# Terminal.net
KiCad netlist of a schematic drawn in Altium Designer
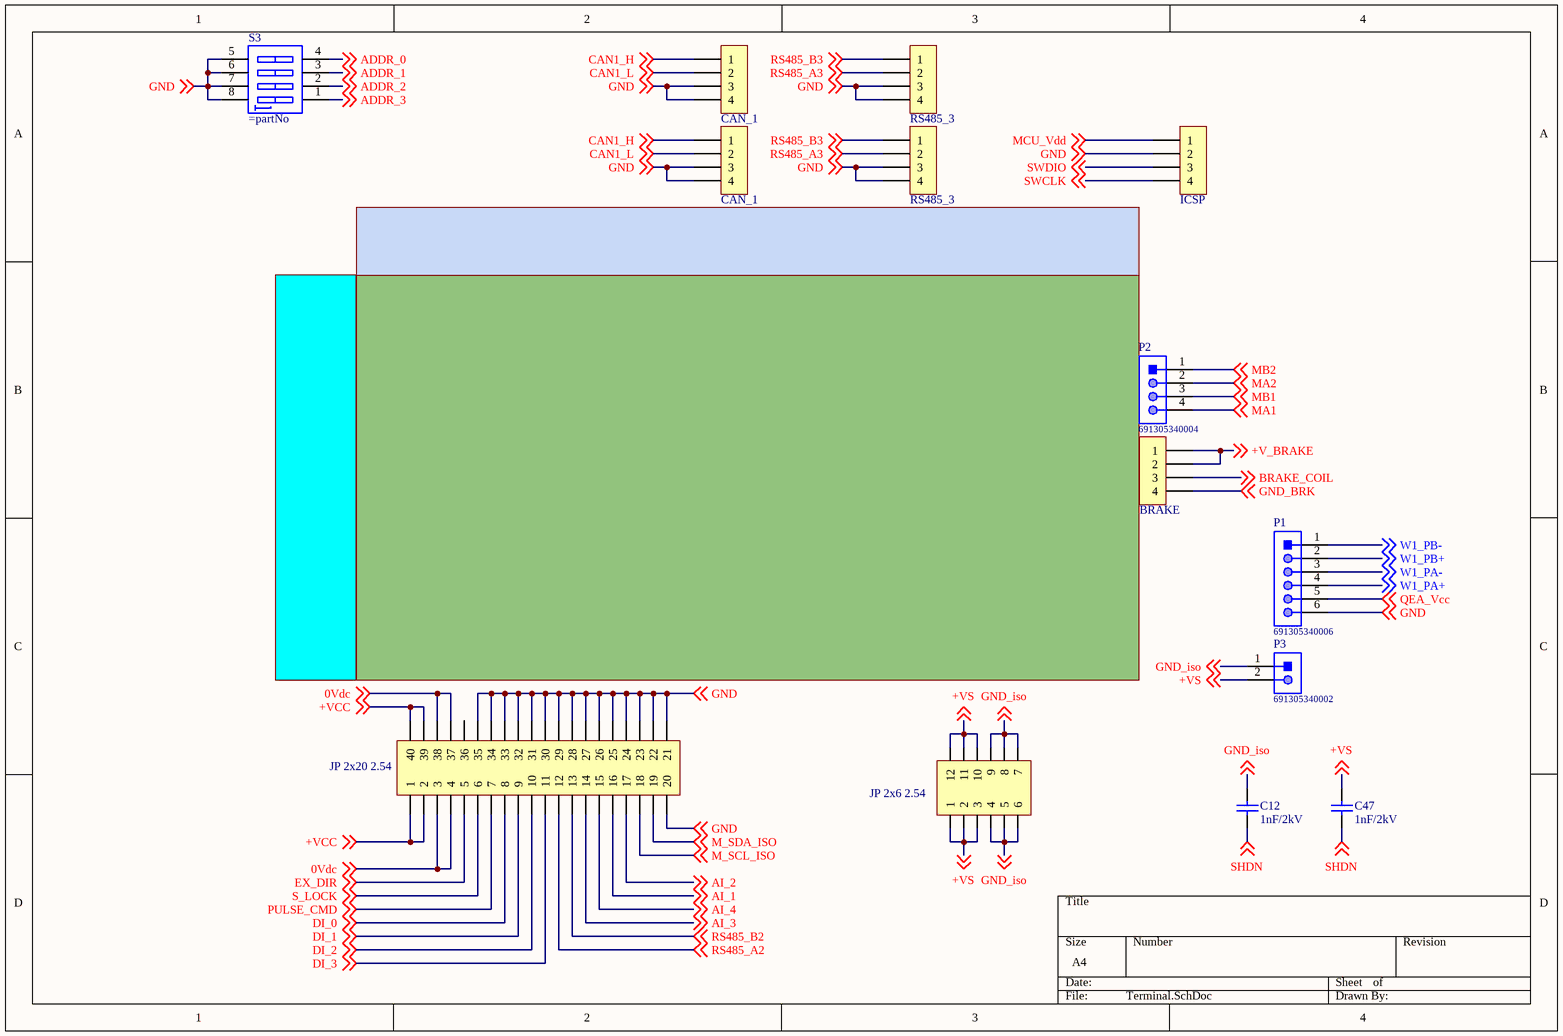
[diagram p0: Terminal.SchDoc]

(export (version "E")
  (design (tool "Eeschema 10.0.6"))
  (components
    (comp (ref "C12")
      (value "1nF/2kV")
      (footprint "Cap 3KV 5mm")
      (description "Capacitor")
      (fields (field (name "PUBLISHER") "Altium Limited"))
      (libsource (lib "DoHuong_sch") (part "Cap"))
    )
    (comp (ref "C47")
      (value "1nF/2kV")
      (footprint "Cap 3KV 5mm")
      (description "Capacitor")
      (fields (field (name "PUBLISHER") "Altium Limited"))
      (libsource (lib "DoHuong_sch") (part "Cap"))
    )
    (comp (ref "H1")
      (value "CAN_1")
      (footprint "Header 4P DC 2.54")
      (description "Cắm")
      (libsource (lib "Header") (part "Header 4P 2.54 Duc Cong"))
    )
    (comp (ref "H2")
      (value "RS485_3")
      (footprint "Header 4P DC 2.54")
      (description "Cắm")
      (libsource (lib "Header") (part "Header 4P 2.54 Duc Cong"))
    )
    (comp (ref "H4")
      (value "ICSP")
      (footprint "Header 4P DC 2.54")
      (description "Cắm")
      (libsource (lib "Header") (part "Header 4P 2.54 Duc Cong"))
    )
    (comp (ref "H5")
      (value "BRAKE")
      (footprint "Header 4P DC 2.54")
      (description "Cắm")
      (libsource (lib "") (part "Header 4P 2.54 Duc Cong_1"))
    )
    (comp (ref "H6")
      (value "CAN_1")
      (footprint "Header 4P DC 2.54")
      (description "Cắm")
      (libsource (lib "Header") (part "Header 4P 2.54 Duc Cong"))
    )
    (comp (ref "H8")
      (value "RS485_3")
      (footprint "Header 4P DC 2.54")
      (description "Cắm")
      (libsource (lib "Header") (part "Header 4P 2.54 Duc Cong"))
    )
    (comp (ref "JP1")
      (value "JP 2x20 2.54")
      (footprint "JP 2x20 DC")
      (description "Cắm")
      (libsource (lib "Jump") (part "JP 2x20 2.54 Duc Cong"))
    )
    (comp (ref "JP2")
      (value "JP 2x6 2.54")
      (footprint "JP 2x6 DC")
      (description "Cắm")
      (libsource (lib "Jump") (part "JP 2x6 2.54 Duc Cong"))
    )
    (comp (ref "P1")
      (value "691305340006")
      (footprint "691305340006")
      (description "Serie 3053 - 3.81mm Horizontal PCB Header with Plastic Latch WR-TBL, 6 pin")
      (fields (field (name "PUBLISHER") "Wurth Elektronik"))
      (libsource (lib "Altium_TBL_Pluggable_PCB_System (rev18a)") (part "691305340006"))
    )
    (comp (ref "P2")
      (value "691305340004")
      (footprint "691305340004")
      (description "Serie 3053 - 3.81mm Horizontal PCB Header with Plastic Latch WR-TBL, 4 pin")
      (fields (field (name "PUBLISHER") "Wurth Elektronik"))
      (libsource (lib "Altium_TBL_Pluggable_PCB_System (rev18a)") (part "691305340004"))
    )
    (comp (ref "P3")
      (value "691305340002")
      (footprint "691305340002")
      (description "Serie 3053 - 3.81mm Horizontal PCB Header with Plastic Latch WR-TBL, 2 pin")
      (fields (field (name "PUBLISHER") "Wurth Elektronik"))
      (libsource (lib "Altium_TBL_Pluggable_PCB_System (rev18a)") (part "691305340002"))
    )
    (comp (ref "S3")
      (value "~")
      (footprint "SW-DIP4")
      (description "WS-DITV 2.54 mm small compact THT flat actuator with top tape")
      (fields
        (field (name "MANUFACTURER") "Wurth Elektronik")
        (field (name "PART NO.") "418127160904")
        (field (name "CREATED BY") "Baojun Chen")
      )
      (libsource (lib "LIBRARY") (part "SWDIP4"))
    )
  )
  (nets
    (net (code "1") (name "+VCC") (class "Default")
      (node (ref "JP1") (pin "1") (pinfunction "1_1") (pintype "passive"))
      (node (ref "JP1") (pin "2") (pinfunction "2_2") (pintype "passive"))
      (node (ref "JP1") (pin "39") (pinfunction "39_39") (pintype "passive"))
      (node (ref "JP1") (pin "40") (pinfunction "40_40") (pintype "passive"))
    )
    (net (code "2") (name "+VS") (class "Default")
      (node (ref "C47") (pin "2") (pinfunction "2_2") (pintype "passive"))
      (node (ref "JP2") (pin "1") (pinfunction "1_1") (pintype "passive"))
      (node (ref "JP2") (pin "10") (pinfunction "10_10") (pintype "passive"))
      (node (ref "JP2") (pin "11") (pinfunction "11_11") (pintype "passive"))
      (node (ref "JP2") (pin "12") (pinfunction "12_12") (pintype "passive"))
      (node (ref "JP2") (pin "2") (pinfunction "2_2") (pintype "passive"))
      (node (ref "JP2") (pin "3") (pinfunction "3_3") (pintype "passive"))
      (node (ref "P3") (pin "2") (pinfunction "2_2") (pintype "passive"))
    )
    (net (code "3") (name "+V_BRAKE") (class "Default")
      (node (ref "H5") (pin "1") (pinfunction "1_1") (pintype "passive"))
      (node (ref "H5") (pin "2") (pinfunction "2_2") (pintype "passive"))
    )
    (net (code "4") (name "0Vdc") (class "Default")
      (node (ref "JP1") (pin "3") (pinfunction "3_3") (pintype "passive"))
      (node (ref "JP1") (pin "37") (pinfunction "37_37") (pintype "passive"))
      (node (ref "JP1") (pin "38") (pinfunction "38_38") (pintype "passive"))
      (node (ref "JP1") (pin "4") (pinfunction "4_4") (pintype "passive"))
    )
    (net (code "5") (name "ADDR_0") (class "Default")
      (node (ref "S3") (pin "4") (pinfunction "4_4") (pintype "passive"))
    )
    (net (code "6") (name "ADDR_1") (class "Default")
      (node (ref "S3") (pin "3") (pinfunction "3_3") (pintype "passive"))
    )
    (net (code "7") (name "ADDR_2") (class "Default")
      (node (ref "S3") (pin "2") (pinfunction "2_2") (pintype "passive"))
    )
    (net (code "8") (name "ADDR_3") (class "Default")
      (node (ref "S3") (pin "1") (pinfunction "1_1") (pintype "passive"))
    )
    (net (code "9") (name "AI_1") (class "Default")
      (node (ref "JP1") (pin "16") (pinfunction "16_16") (pintype "passive"))
    )
    (net (code "10") (name "AI_2") (class "Default")
      (node (ref "JP1") (pin "17") (pinfunction "17_17") (pintype "passive"))
    )
    (net (code "11") (name "AI_3") (class "Default")
      (node (ref "JP1") (pin "14") (pinfunction "14_14") (pintype "passive"))
    )
    (net (code "12") (name "AI_4") (class "Default")
      (node (ref "JP1") (pin "15") (pinfunction "15_15") (pintype "passive"))
    )
    (net (code "13") (name "BRAKE_COIL") (class "Default")
      (node (ref "H5") (pin "3") (pinfunction "3_3") (pintype "passive"))
    )
    (net (code "14") (name "CAN1_H") (class "Default")
      (node (ref "H1") (pin "1") (pinfunction "1_1") (pintype "passive"))
      (node (ref "H6") (pin "1") (pinfunction "1_1") (pintype "passive"))
    )
    (net (code "15") (name "CAN1_L") (class "Default")
      (node (ref "H1") (pin "2") (pinfunction "2_2") (pintype "passive"))
      (node (ref "H6") (pin "2") (pinfunction "2_2") (pintype "passive"))
    )
    (net (code "16") (name "DI_0") (class "Default")
      (node (ref "JP1") (pin "8") (pinfunction "8_8") (pintype "passive"))
    )
    (net (code "17") (name "DI_1") (class "Default")
      (node (ref "JP1") (pin "9") (pinfunction "9_9") (pintype "passive"))
    )
    (net (code "18") (name "DI_2") (class "Default")
      (node (ref "JP1") (pin "10") (pinfunction "10_10") (pintype "passive"))
    )
    (net (code "19") (name "DI_3") (class "Default")
      (node (ref "JP1") (pin "11") (pinfunction "11_11") (pintype "passive"))
    )
    (net (code "20") (name "EX_DIR") (class "Default")
      (node (ref "JP1") (pin "5") (pinfunction "5_5") (pintype "passive"))
    )
    (net (code "21") (name "GND") (class "Default")
      (node (ref "H1") (pin "3") (pinfunction "3_3") (pintype "passive"))
      (node (ref "H1") (pin "4") (pinfunction "4_4") (pintype "passive"))
      (node (ref "H2") (pin "3") (pinfunction "3_3") (pintype "passive"))
      (node (ref "H2") (pin "4") (pinfunction "4_4") (pintype "passive"))
      (node (ref "H4") (pin "2") (pinfunction "2_2") (pintype "passive"))
      (node (ref "H6") (pin "3") (pinfunction "3_3") (pintype "passive"))
      (node (ref "H6") (pin "4") (pinfunction "4_4") (pintype "passive"))
      (node (ref "H8") (pin "3") (pinfunction "3_3") (pintype "passive"))
      (node (ref "H8") (pin "4") (pinfunction "4_4") (pintype "passive"))
      (node (ref "JP1") (pin "20") (pinfunction "20_20") (pintype "passive"))
      (node (ref "JP1") (pin "21") (pinfunction "21_21") (pintype "passive"))
      (node (ref "JP1") (pin "22") (pinfunction "22_22") (pintype "passive"))
      (node (ref "JP1") (pin "23") (pinfunction "23_23") (pintype "passive"))
      (node (ref "JP1") (pin "24") (pinfunction "24_24") (pintype "passive"))
      (node (ref "JP1") (pin "25") (pinfunction "25_25") (pintype "passive"))
      (node (ref "JP1") (pin "26") (pinfunction "26_26") (pintype "passive"))
      (node (ref "JP1") (pin "27") (pinfunction "27_27") (pintype "passive"))
      (node (ref "JP1") (pin "28") (pinfunction "28_28") (pintype "passive"))
      (node (ref "JP1") (pin "29") (pinfunction "29_29") (pintype "passive"))
      (node (ref "JP1") (pin "30") (pinfunction "30_30") (pintype "passive"))
      (node (ref "JP1") (pin "31") (pinfunction "31_31") (pintype "passive"))
      (node (ref "JP1") (pin "32") (pinfunction "32_32") (pintype "passive"))
      (node (ref "JP1") (pin "33") (pinfunction "33_33") (pintype "passive"))
      (node (ref "JP1") (pin "34") (pinfunction "34_34") (pintype "passive"))
      (node (ref "JP1") (pin "35") (pinfunction "35_35") (pintype "passive"))
      (node (ref "P1") (pin "6") (pinfunction "6_6") (pintype "passive"))
      (node (ref "S3") (pin "5") (pinfunction "5_5") (pintype "passive"))
      (node (ref "S3") (pin "6") (pinfunction "6_6") (pintype "passive"))
      (node (ref "S3") (pin "7") (pinfunction "7_7") (pintype "passive"))
      (node (ref "S3") (pin "8") (pinfunction "8_8") (pintype "passive"))
    )
    (net (code "22") (name "GND_BRK") (class "Default")
      (node (ref "H5") (pin "4") (pinfunction "4_4") (pintype "passive"))
    )
    (net (code "23") (name "GND_iso") (class "Default")
      (node (ref "C12") (pin "2") (pinfunction "2_2") (pintype "passive"))
      (node (ref "JP2") (pin "4") (pinfunction "4_4") (pintype "passive"))
      (node (ref "JP2") (pin "5") (pinfunction "5_5") (pintype "passive"))
      (node (ref "JP2") (pin "6") (pinfunction "6_6") (pintype "passive"))
      (node (ref "JP2") (pin "7") (pinfunction "7_7") (pintype "passive"))
      (node (ref "JP2") (pin "8") (pinfunction "8_8") (pintype "passive"))
      (node (ref "JP2") (pin "9") (pinfunction "9_9") (pintype "passive"))
      (node (ref "P3") (pin "1") (pinfunction "1_1") (pintype "passive"))
    )
    (net (code "24") (name "MA1") (class "Default")
      (node (ref "P2") (pin "4") (pinfunction "4_4") (pintype "passive"))
    )
    (net (code "25") (name "MA2") (class "Default")
      (node (ref "P2") (pin "2") (pinfunction "2_2") (pintype "passive"))
    )
    (net (code "26") (name "MB1") (class "Default")
      (node (ref "P2") (pin "3") (pinfunction "3_3") (pintype "passive"))
    )
    (net (code "27") (name "MB2") (class "Default")
      (node (ref "P2") (pin "1") (pinfunction "1_1") (pintype "passive"))
    )
    (net (code "28") (name "MCU_Vdd") (class "Default")
      (node (ref "H4") (pin "1") (pinfunction "1_1") (pintype "passive"))
    )
    (net (code "29") (name "M_SCL_ISO") (class "Default")
      (node (ref "JP1") (pin "18") (pinfunction "18_18") (pintype "passive"))
    )
    (net (code "30") (name "M_SDA_ISO") (class "Default")
      (node (ref "JP1") (pin "19") (pinfunction "19_19") (pintype "passive"))
    )
    (net (code "31") (name "PULSE_CMD") (class "Default")
      (node (ref "JP1") (pin "7") (pinfunction "7_7") (pintype "passive"))
    )
    (net (code "32") (name "QEA_Vcc") (class "Default")
      (node (ref "P1") (pin "5") (pinfunction "5_5") (pintype "passive"))
    )
    (net (code "33") (name "RS485_A2") (class "Default")
      (node (ref "JP1") (pin "12") (pinfunction "12_12") (pintype "passive"))
    )
    (net (code "34") (name "RS485_A3") (class "Default")
      (node (ref "H2") (pin "2") (pinfunction "2_2") (pintype "passive"))
      (node (ref "H8") (pin "2") (pinfunction "2_2") (pintype "passive"))
    )
    (net (code "35") (name "RS485_B2") (class "Default")
      (node (ref "JP1") (pin "13") (pinfunction "13_13") (pintype "passive"))
    )
    (net (code "36") (name "RS485_B3") (class "Default")
      (node (ref "H2") (pin "1") (pinfunction "1_1") (pintype "passive"))
      (node (ref "H8") (pin "1") (pinfunction "1_1") (pintype "passive"))
    )
    (net (code "37") (name "SHDN") (class "Default")
      (node (ref "C12") (pin "1") (pinfunction "1_1") (pintype "passive"))
      (node (ref "C47") (pin "1") (pinfunction "1_1") (pintype "passive"))
    )
    (net (code "38") (name "SWCLK") (class "Default")
      (node (ref "H4") (pin "4") (pinfunction "4_4") (pintype "passive"))
    )
    (net (code "39") (name "SWDIO") (class "Default")
      (node (ref "H4") (pin "3") (pinfunction "3_3") (pintype "passive"))
    )
    (net (code "40") (name "S_LOCK") (class "Default")
      (node (ref "JP1") (pin "6") (pinfunction "6_6") (pintype "passive"))
    )
    (net (code "41") (name "W1_PA+") (class "Default")
      (node (ref "P1") (pin "4") (pinfunction "4_4") (pintype "passive"))
    )
    (net (code "42") (name "W1_PA-") (class "Default")
      (node (ref "P1") (pin "3") (pinfunction "3_3") (pintype "passive"))
    )
    (net (code "43") (name "W1_PB+") (class "Default")
      (node (ref "P1") (pin "2") (pinfunction "2_2") (pintype "passive"))
    )
    (net (code "44") (name "W1_PB-") (class "Default")
      (node (ref "P1") (pin "1") (pinfunction "1_1") (pintype "passive"))
    )
    (net (code "45") (name "unconnected-(JP1-Pad36)") (class "Default")
      (node (ref "JP1") (pin "36") (pinfunction "36_36") (pintype "passive"))
    )
  )
)
